# RotaryController2.net
KiCad netlist of a schematic drawn in Altium Designer
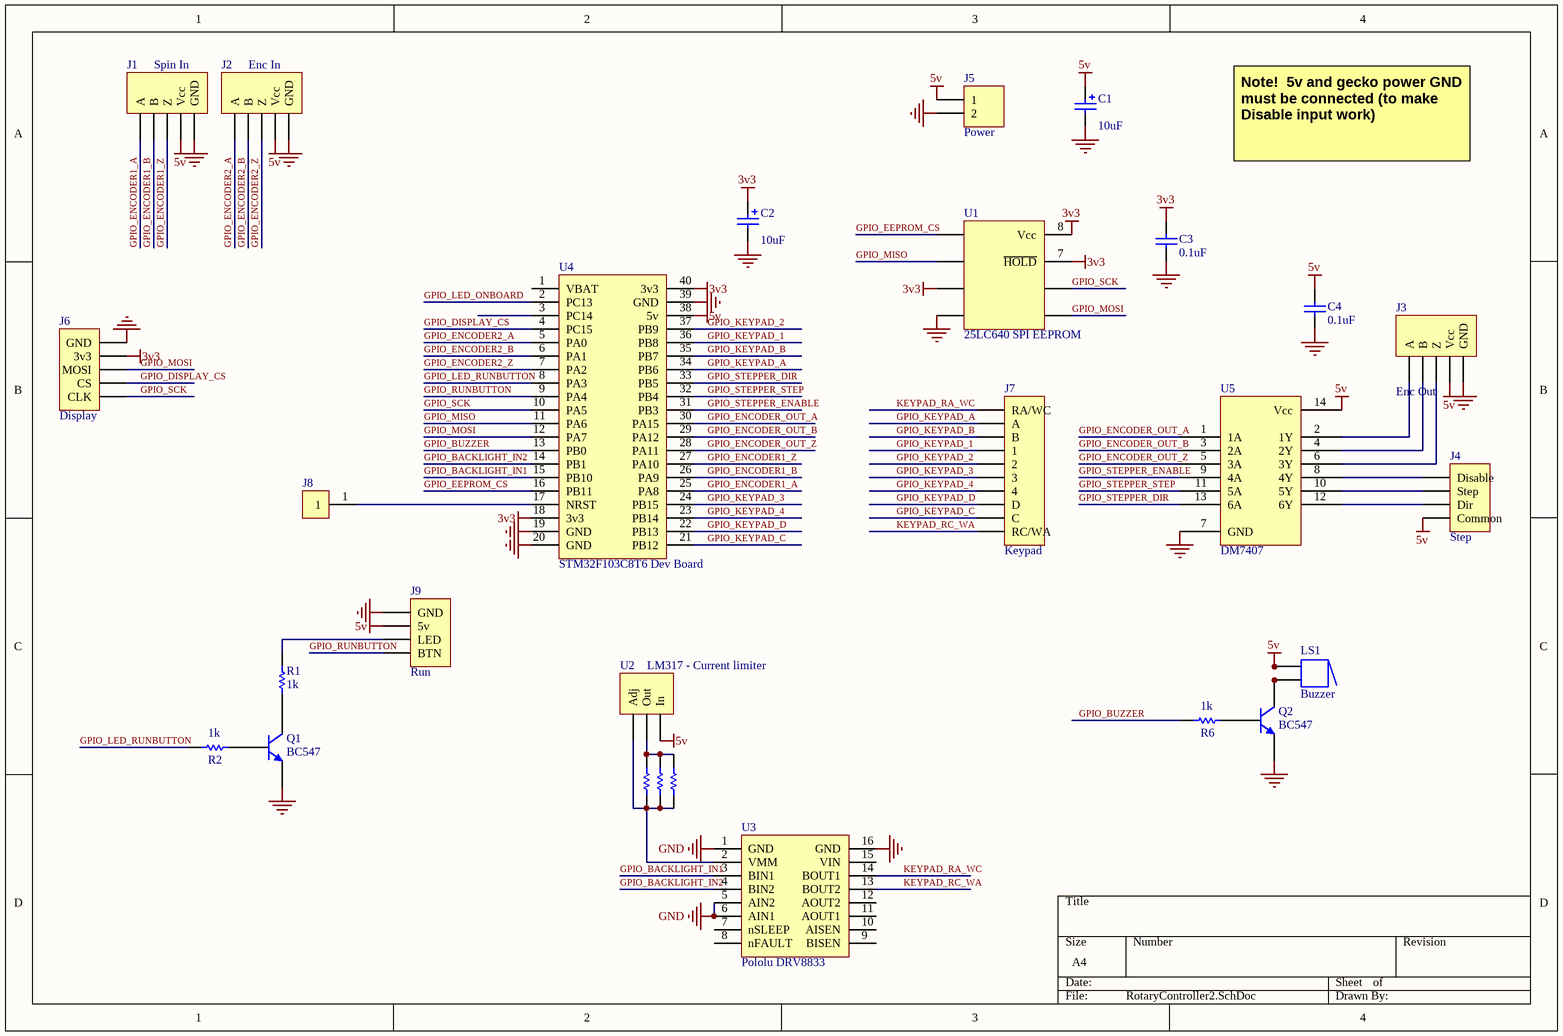
[diagram p0: RotaryController2.SchDoc]

(export (version "E")
  (design (tool "Eeschema 10.0.6"))
  (components
    (comp (ref "C1")
      (value "10uF")
      (footprint "Cap Cyl 14x5 2.5")
      (description "Polarized Capacitor (Radial)")
      (fields (field (name "Comment") "Cap Pol") (field (name "PUBLISHER") "Altium Limited"))
      (libsource (lib "Custom") (part "Cap Pol"))
    )
    (comp (ref "C2")
      (value "10uF")
      (footprint "Cap Cyl 14x5 2.5")
      (description "Polarized Capacitor (Radial)")
      (fields (field (name "Comment") "Cap Pol") (field (name "PUBLISHER") "Altium Limited"))
      (libsource (lib "Custom") (part "Cap Pol"))
    )
    (comp (ref "C3")
      (value "0.1uF")
      (footprint "Cap Monolithic 2.5")
      (description "Capacitor")
      (fields (field (name "Comment") "Cap") (field (name "PUBLISHER") "Altium Limited"))
      (libsource (lib "Custom") (part "Cap"))
    )
    (comp (ref "C4")
      (value "0.1uF")
      (footprint "Cap Monolithic 2.5")
      (description "Capacitor")
      (fields (field (name "Comment") "Cap") (field (name "PUBLISHER") "Altium Limited"))
      (libsource (lib "Custom") (part "Cap"))
    )
    (comp (ref "J1")
      (value "Spin In")
      (footprint "0.1 SIP 5 PIN")
      (description "Header, 5-Pin")
      (fields (field (name "PUBLISHER") "Altium Limited"))
      (libsource (lib "Miscellaneous Connectors") (part "Header 5"))
    )
    (comp (ref "J2")
      (value "Enc In")
      (footprint "0.1 SIP 5 PIN")
      (description "Header, 5-Pin")
      (fields (field (name "PUBLISHER") "Altium Limited"))
      (libsource (lib "Miscellaneous Connectors") (part "Header 5"))
    )
    (comp (ref "J3")
      (value "Enc Out")
      (footprint "0.1 SIP 5 PIN")
      (description "Header, 5-Pin")
      (fields (field (name "PUBLISHER") "Altium Limited"))
      (libsource (lib "Miscellaneous Connectors") (part "Header 5"))
    )
    (comp (ref "J4")
      (value "Step")
      (footprint "0.1 SIP 4 PIN")
      (description "Header, 4-Pin")
      (fields (field (name "PUBLISHER") "Altium Limited"))
      (libsource (lib "Miscellaneous Connectors") (part "Header 4"))
    )
    (comp (ref "J5")
      (value "Power")
      (footprint "0.156 SIP 2 PIN")
      (description "Header, 2-Pin")
      (fields (field (name "PUBLISHER") "Altium Limited"))
      (libsource (lib "Miscellaneous Connectors") (part "Header 2"))
    )
    (comp (ref "J6")
      (value "Display")
      (footprint "0.1 SIP 5 PIN")
      (description "Header, 5-Pin")
      (fields (field (name "PUBLISHER") "Altium Limited"))
      (libsource (lib "") (part "Header 5_1"))
    )
    (comp (ref "J7")
      (value "Keypad")
      (footprint "0.1 SIP 10 PIN")
      (description "Header, 10-Pin")
      (fields (field (name "PUBLISHER") "Altium Limited"))
      (libsource (lib "Miscellaneous Connectors") (part "Header 10"))
    )
    (comp (ref "J8") (value "HDR 1") (footprint "HDR1") (libsource (lib "Custom") (part "Header 1")))
    (comp (ref "J9")
      (value "Run")
      (footprint "0.1 SIP 4 PIN")
      (description "Header, 4-Pin")
      (fields (field (name "PUBLISHER") "Altium Limited"))
      (libsource (lib "Miscellaneous Connectors") (part "Header 4"))
    )
    (comp (ref "LS1")
      (value "Buzzer")
      (footprint "Buzzer Mini PC Mount Piezo 14x7.5")
      (description "Magnetic Transducer Buzzer")
      (fields (field (name "PUBLISHER") "Altium Limited"))
      (libsource (lib "Miscellaneous Devices") (part "Buzzer"))
    )
    (comp (ref "Q1")
      (value "BC547")
      (footprint "TO-92 0.05\"")
      (description "General Purpose Amplifier NPN Silicon")
      (fields (field (name "PUBLISHER") "Altium Limited"))
      (libsource (lib "Custom") (part "MMBT100A"))
    )
    (comp (ref "Q2")
      (value "BC547")
      (footprint "TO-92 0.05\"")
      (description "General Purpose Amplifier NPN Silicon")
      (fields (field (name "PUBLISHER") "Altium Limited"))
      (libsource (lib "Custom") (part "MMBT100A"))
    )
    (comp (ref "R1")
      (value "1k")
      (footprint "Resistor Axial 1/4W 0.4")
      (fields (field (name "Comment") "Res1"))
      (libsource (lib "Custom") (part "Resistor"))
    )
    (comp (ref "R2")
      (value "1k")
      (footprint "Resistor Axial 1/4W 0.4")
      (fields (field (name "Comment") "Res1"))
      (libsource (lib "Custom") (part "Resistor"))
    )
    (comp (ref "R3")
      (value "Res1")
      (footprint "Resistor Axial 1/4W 0.4")
      (libsource (lib "Custom") (part "Resistor"))
    )
    (comp (ref "R4")
      (value "Res1")
      (footprint "Resistor Axial 1/4W 0.4")
      (libsource (lib "Custom") (part "Resistor"))
    )
    (comp (ref "R5")
      (value "Res1")
      (footprint "Resistor Axial 1/4W 0.4")
      (libsource (lib "Custom") (part "Resistor"))
    )
    (comp (ref "R6")
      (value "1k")
      (footprint "Resistor Axial 1/4W 0.4")
      (fields (field (name "Comment") "Res1"))
      (libsource (lib "Custom") (part "Resistor"))
    )
    (comp (ref "U1")
      (value "25LC640 SPI EEPROM")
      (footprint "DIP8")
      (libsource (lib "Custom") (part "25LC640"))
    )
    (comp (ref "U2")
      (value "LM317 - Current limiter")
      (footprint "TO-220")
      (description "Header, 3-Pin")
      (fields (field (name "PUBLISHER") "Altium Limited"))
      (libsource (lib "Miscellaneous Connectors") (part "Header 3"))
    )
    (comp (ref "U3")
      (value "Pololu DRV8833")
      (footprint "Pololu DRV8833")
      (description "Pololu DRV8833 Dual Motor Driver Carrier")
      (libsource (lib "Custom") (part "Pololu DRV8833"))
    )
    (comp (ref "U4")
      (value "STM32F103C8T6 Dev Board")
      (footprint "STM32F103C8T6 Dev Board")
      (libsource (lib "Custom") (part "STM32F103C8T6 Dev Board"))
    )
    (comp (ref "U5")
      (value "DM7407")
      (footprint "DIP14")
      (description "Hex Buffer with Open Collector Outputs")
      (libsource (lib "Custom") (part "74xx07"))
    )
  )
  (nets
    (net (code "1") (name "/GPIO_BACKLIGHT_IN1") (class "Default")
      (node (ref "U3") (pin "3") (pinfunction "BIN1_3") (pintype "passive"))
      (node (ref "U4") (pin "15") (pinfunction "PB10_15") (pintype "passive"))
    )
    (net (code "2") (name "/GPIO_BACKLIGHT_IN2") (class "Default")
      (node (ref "U3") (pin "4") (pinfunction "BIN2_4") (pintype "passive"))
      (node (ref "U4") (pin "14") (pinfunction "PB1_14") (pintype "passive"))
    )
    (net (code "3") (name "/GPIO_BUZZER") (class "Default")
      (node (ref "R6") (pin "1") (pinfunction "1_1") (pintype "passive"))
      (node (ref "U4") (pin "13") (pinfunction "PB0_13") (pintype "passive"))
    )
    (net (code "4") (name "/GPIO_DISPLAY_CS") (class "Default")
      (node (ref "J6") (pin "2") (pinfunction "CS_2") (pintype "passive"))
      (node (ref "U4") (pin "4") (pinfunction "PC15_4") (pintype "passive"))
    )
    (net (code "5") (name "/GPIO_EEPROM_CS") (class "Default")
      (node (ref "U1") (pin "1") (pinfunction "~{CS}_1") (pintype "passive"))
      (node (ref "U4") (pin "16") (pinfunction "PB11_16") (pintype "passive"))
    )
    (net (code "6") (name "/GPIO_ENCODER1_A") (class "Default")
      (node (ref "J1") (pin "1") (pinfunction "A_1") (pintype "passive"))
      (node (ref "U4") (pin "25") (pinfunction "PA8_25") (pintype "passive"))
    )
    (net (code "7") (name "/GPIO_ENCODER1_B") (class "Default")
      (node (ref "J1") (pin "2") (pinfunction "B_2") (pintype "passive"))
      (node (ref "U4") (pin "26") (pinfunction "PA9_26") (pintype "passive"))
    )
    (net (code "8") (name "/GPIO_ENCODER1_Z") (class "Default")
      (node (ref "J1") (pin "3") (pinfunction "Z_3") (pintype "passive"))
      (node (ref "U4") (pin "27") (pinfunction "PA10_27") (pintype "passive"))
    )
    (net (code "9") (name "/GPIO_ENCODER2_A") (class "Default")
      (node (ref "J2") (pin "1") (pinfunction "A_1") (pintype "passive"))
      (node (ref "U4") (pin "5") (pinfunction "PA0_5") (pintype "passive"))
    )
    (net (code "10") (name "/GPIO_ENCODER2_B") (class "Default")
      (node (ref "J2") (pin "2") (pinfunction "B_2") (pintype "passive"))
      (node (ref "U4") (pin "6") (pinfunction "PA1_6") (pintype "passive"))
    )
    (net (code "11") (name "/GPIO_ENCODER2_Z") (class "Default")
      (node (ref "J2") (pin "3") (pinfunction "Z_3") (pintype "passive"))
      (node (ref "U4") (pin "7") (pinfunction "PA2_7") (pintype "passive"))
    )
    (net (code "12") (name "/GPIO_ENCODER_OUT_A") (class "Default")
      (node (ref "U4") (pin "30") (pinfunction "PA15_30") (pintype "passive"))
      (node (ref "U5") (pin "1") (pinfunction "1A_1") (pintype "passive"))
    )
    (net (code "13") (name "/GPIO_ENCODER_OUT_B") (class "Default")
      (node (ref "U4") (pin "29") (pinfunction "PA12_29") (pintype "passive"))
      (node (ref "U5") (pin "3") (pinfunction "2A_3") (pintype "passive"))
    )
    (net (code "14") (name "/GPIO_ENCODER_OUT_Z") (class "Default")
      (node (ref "U4") (pin "28") (pinfunction "PA11_28") (pintype "passive"))
      (node (ref "U5") (pin "5") (pinfunction "3A_5") (pintype "passive"))
    )
    (net (code "15") (name "/GPIO_KEYPAD_1") (class "Default")
      (node (ref "J7") (pin "4") (pinfunction "1_4") (pintype "passive"))
      (node (ref "U4") (pin "36") (pinfunction "PB8_36") (pintype "passive"))
    )
    (net (code "16") (name "/GPIO_KEYPAD_2") (class "Default")
      (node (ref "J7") (pin "5") (pinfunction "2_5") (pintype "passive"))
      (node (ref "U4") (pin "37") (pinfunction "PB9_37") (pintype "passive"))
    )
    (net (code "17") (name "/GPIO_KEYPAD_3") (class "Default")
      (node (ref "J7") (pin "6") (pinfunction "3_6") (pintype "passive"))
      (node (ref "U4") (pin "24") (pinfunction "PB15_24") (pintype "passive"))
    )
    (net (code "18") (name "/GPIO_KEYPAD_4") (class "Default")
      (node (ref "J7") (pin "7") (pinfunction "4_7") (pintype "passive"))
      (node (ref "U4") (pin "23") (pinfunction "PB14_23") (pintype "passive"))
    )
    (net (code "19") (name "/GPIO_KEYPAD_A") (class "Default")
      (node (ref "J7") (pin "2") (pinfunction "A_2") (pintype "passive"))
      (node (ref "U4") (pin "34") (pinfunction "PB6_34") (pintype "passive"))
    )
    (net (code "20") (name "/GPIO_KEYPAD_B") (class "Default")
      (node (ref "J7") (pin "3") (pinfunction "B_3") (pintype "passive"))
      (node (ref "U4") (pin "35") (pinfunction "PB7_35") (pintype "passive"))
    )
    (net (code "21") (name "/GPIO_KEYPAD_C") (class "Default")
      (node (ref "J7") (pin "9") (pinfunction "C_9") (pintype "passive"))
      (node (ref "U4") (pin "21") (pinfunction "PB12_21") (pintype "passive"))
    )
    (net (code "22") (name "/GPIO_KEYPAD_D") (class "Default")
      (node (ref "J7") (pin "8") (pinfunction "D_8") (pintype "passive"))
      (node (ref "U4") (pin "22") (pinfunction "PB13_22") (pintype "passive"))
    )
    (net (code "23") (name "/GPIO_LED_ONBOARD") (class "Default")
      (node (ref "U4") (pin "2") (pinfunction "PC13_2") (pintype "passive"))
    )
    (net (code "24") (name "/GPIO_LED_RUNBUTTON") (class "Default")
      (node (ref "R2") (pin "1") (pinfunction "1_1") (pintype "passive"))
      (node (ref "U4") (pin "8") (pinfunction "PA3_8") (pintype "passive"))
    )
    (net (code "25") (name "/GPIO_MISO") (class "Default")
      (node (ref "U1") (pin "2") (pinfunction "SO_2") (pintype "passive"))
      (node (ref "U4") (pin "11") (pinfunction "PA6_11") (pintype "passive"))
    )
    (net (code "26") (name "/GPIO_MOSI") (class "Default")
      (node (ref "J6") (pin "3") (pinfunction "MOSI_3") (pintype "passive"))
      (node (ref "U1") (pin "5") (pinfunction "SI_5") (pintype "passive"))
      (node (ref "U4") (pin "12") (pinfunction "PA7_12") (pintype "passive"))
    )
    (net (code "27") (name "/GPIO_RUNBUTTON") (class "Default")
      (node (ref "J9") (pin "4") (pinfunction "Common_4") (pintype "passive"))
      (node (ref "U4") (pin "9") (pinfunction "PA4_9") (pintype "passive"))
    )
    (net (code "28") (name "/GPIO_SCK") (class "Default")
      (node (ref "J6") (pin "1") (pinfunction "CLK_1") (pintype "passive"))
      (node (ref "U1") (pin "6") (pinfunction "SCK_6") (pintype "passive"))
      (node (ref "U4") (pin "10") (pinfunction "PA5_10") (pintype "passive"))
    )
    (net (code "29") (name "/GPIO_STEPPER_DIR") (class "Default")
      (node (ref "U4") (pin "33") (pinfunction "PB5_33") (pintype "passive"))
      (node (ref "U5") (pin "13") (pinfunction "6A_13") (pintype "passive"))
    )
    (net (code "30") (name "/GPIO_STEPPER_ENABLE") (class "Default")
      (node (ref "U4") (pin "31") (pinfunction "PB3_31") (pintype "passive"))
      (node (ref "U5") (pin "9") (pinfunction "4A_9") (pintype "passive"))
    )
    (net (code "31") (name "/GPIO_STEPPER_STEP") (class "Default")
      (node (ref "U4") (pin "32") (pinfunction "PB4_32") (pintype "passive"))
      (node (ref "U5") (pin "11") (pinfunction "5A_11") (pintype "passive"))
    )
    (net (code "32") (name "/KEYPAD_RA_WC") (class "Default")
      (node (ref "J7") (pin "1") (pinfunction "RA/WC_1") (pintype "passive"))
      (node (ref "U3") (pin "14") (pinfunction "BOUT1_14") (pintype "passive"))
    )
    (net (code "33") (name "/KEYPAD_RC_WA") (class "Default")
      (node (ref "J7") (pin "10") (pinfunction "RC/WA_10") (pintype "passive"))
      (node (ref "U3") (pin "13") (pinfunction "BOUT2_13") (pintype "passive"))
    )
    (net (code "34") (name "3v3") (class "Default")
      (node (ref "C2") (pin "1") (pinfunction "1_1") (pintype "passive"))
      (node (ref "C3") (pin "2") (pinfunction "2_2") (pintype "passive"))
      (node (ref "J6") (pin "4") (pinfunction "3v3_4") (pintype "passive"))
      (node (ref "U1") (pin "3") (pinfunction "~{WP}_3") (pintype "passive"))
      (node (ref "U1") (pin "7") (pinfunction "~{HOLD}_7") (pintype "power_in"))
      (node (ref "U1") (pin "8") (pinfunction "Vcc_8") (pintype "power_in"))
      (node (ref "U4") (pin "18") (pinfunction "3v3_18") (pintype "passive"))
      (node (ref "U4") (pin "40") (pinfunction "3v3_40") (pintype "passive"))
    )
    (net (code "35") (name "5v") (class "Default")
      (node (ref "C1") (pin "1") (pinfunction "1_1") (pintype "passive"))
      (node (ref "C4") (pin "2") (pinfunction "2_2") (pintype "passive"))
      (node (ref "J1") (pin "4") (pinfunction "Vcc_4") (pintype "passive"))
      (node (ref "J2") (pin "4") (pinfunction "Vcc_4") (pintype "passive"))
      (node (ref "J3") (pin "4") (pinfunction "Vcc_4") (pintype "passive"))
      (node (ref "J4") (pin "4") (pinfunction "Common_4") (pintype "passive"))
      (node (ref "J5") (pin "1") (pinfunction "1_1") (pintype "passive"))
      (node (ref "J9") (pin "2") (pinfunction "Step_2") (pintype "passive"))
      (node (ref "LS1") (pin "1") (pinfunction "1_1") (pintype "passive"))
      (node (ref "LS1") (pin "1A") (pinfunction "1A_1A") (pintype "passive"))
      (node (ref "U2") (pin "3") (pinfunction "In_3") (pintype "passive"))
      (node (ref "U4") (pin "38") (pinfunction "5v_38") (pintype "passive"))
      (node (ref "U5") (pin "14") (pinfunction "Vcc_14") (pintype "passive"))
    )
    (net (code "36") (name "GND") (class "Default")
      (node (ref "C1") (pin "2") (pinfunction "2_2") (pintype "passive"))
      (node (ref "C2") (pin "2") (pinfunction "2_2") (pintype "passive"))
      (node (ref "C3") (pin "1") (pinfunction "1_1") (pintype "passive"))
      (node (ref "C4") (pin "1") (pinfunction "1_1") (pintype "passive"))
      (node (ref "J1") (pin "5") (pinfunction "GND_5") (pintype "passive"))
      (node (ref "J2") (pin "5") (pinfunction "GND_5") (pintype "passive"))
      (node (ref "J3") (pin "5") (pinfunction "GND_5") (pintype "passive"))
      (node (ref "J5") (pin "2") (pinfunction "2_2") (pintype "passive"))
      (node (ref "J6") (pin "5") (pinfunction "GND_5") (pintype "passive"))
      (node (ref "J9") (pin "1") (pinfunction "Disable_1") (pintype "passive"))
      (node (ref "Q1") (pin "E") (pinfunction "E_E") (pintype "passive"))
      (node (ref "Q2") (pin "E") (pinfunction "E_E") (pintype "passive"))
      (node (ref "U1") (pin "4") (pinfunction "Vss_4") (pintype "passive"))
      (node (ref "U3") (pin "1") (pinfunction "GND_1") (pintype "passive"))
      (node (ref "U3") (pin "16") (pinfunction "GND_16") (pintype "passive"))
      (node (ref "U3") (pin "5") (pinfunction "AIN2_5") (pintype "passive"))
      (node (ref "U3") (pin "6") (pinfunction "AIN1_6") (pintype "passive"))
      (node (ref "U4") (pin "19") (pinfunction "GND_19") (pintype "passive"))
      (node (ref "U4") (pin "20") (pinfunction "GND_20") (pintype "passive"))
      (node (ref "U4") (pin "39") (pinfunction "GND_39") (pintype "passive"))
      (node (ref "U5") (pin "7") (pinfunction "GND_7") (pintype "passive"))
    )
    (net (code "37") (name "Net-(J3-A)") (class "Default")
      (node (ref "J3") (pin "1") (pinfunction "A_1") (pintype "passive"))
      (node (ref "U5") (pin "2") (pinfunction "1Y_2") (pintype "passive"))
    )
    (net (code "38") (name "Net-(J3-B)") (class "Default")
      (node (ref "J3") (pin "2") (pinfunction "B_2") (pintype "passive"))
      (node (ref "U5") (pin "4") (pinfunction "2Y_4") (pintype "passive"))
    )
    (net (code "39") (name "Net-(J3-Z)") (class "Default")
      (node (ref "J3") (pin "3") (pinfunction "Z_3") (pintype "passive"))
      (node (ref "U5") (pin "6") (pinfunction "3Y_6") (pintype "passive"))
    )
    (net (code "40") (name "Net-(J4-Dir)") (class "Default")
      (node (ref "J4") (pin "3") (pinfunction "Dir_3") (pintype "passive"))
      (node (ref "U5") (pin "12") (pinfunction "6Y_12") (pintype "passive"))
    )
    (net (code "41") (name "Net-(J4-Disable)") (class "Default")
      (node (ref "J4") (pin "1") (pinfunction "Disable_1") (pintype "passive"))
      (node (ref "U5") (pin "8") (pinfunction "4Y_8") (pintype "passive"))
    )
    (net (code "42") (name "Net-(J4-Step)") (class "Default")
      (node (ref "J4") (pin "2") (pinfunction "Step_2") (pintype "passive"))
      (node (ref "U5") (pin "10") (pinfunction "5Y_10") (pintype "passive"))
    )
    (net (code "43") (name "Net-(J9-Dir)") (class "Default")
      (node (ref "J9") (pin "3") (pinfunction "Dir_3") (pintype "passive"))
      (node (ref "R1") (pin "1") (pinfunction "1_1") (pintype "passive"))
    )
    (net (code "44") (name "Net-(LS1-Pad2)") (class "Default")
      (node (ref "LS1") (pin "2") (pinfunction "2_2") (pintype "passive"))
      (node (ref "LS1") (pin "2A") (pinfunction "2A_2A") (pintype "passive"))
      (node (ref "Q2") (pin "C") (pinfunction "C_C") (pintype "passive"))
    )
    (net (code "45") (name "Net-(Q1-PadB)") (class "Default")
      (node (ref "Q1") (pin "B") (pinfunction "B_B") (pintype "passive"))
      (node (ref "R2") (pin "2") (pinfunction "2_2") (pintype "passive"))
    )
    (net (code "46") (name "Net-(Q1-PadC)") (class "Default")
      (node (ref "Q1") (pin "C") (pinfunction "C_C") (pintype "passive"))
      (node (ref "R1") (pin "2") (pinfunction "2_2") (pintype "passive"))
    )
    (net (code "47") (name "Net-(Q2-PadB)") (class "Default")
      (node (ref "Q2") (pin "B") (pinfunction "B_B") (pintype "passive"))
      (node (ref "R6") (pin "2") (pinfunction "2_2") (pintype "passive"))
    )
    (net (code "48") (name "Net-(U2-Adj)") (class "Default")
      (node (ref "R3") (pin "2") (pinfunction "2_2") (pintype "passive"))
      (node (ref "R4") (pin "2") (pinfunction "2_2") (pintype "passive"))
      (node (ref "R5") (pin "2") (pinfunction "2_2") (pintype "passive"))
      (node (ref "U2") (pin "1") (pinfunction "Adj_1") (pintype "passive"))
      (node (ref "U3") (pin "2") (pinfunction "VMM_2") (pintype "passive"))
    )
    (net (code "49") (name "Net-(U2-Out)") (class "Default")
      (node (ref "R3") (pin "1") (pinfunction "1_1") (pintype "passive"))
      (node (ref "R4") (pin "1") (pinfunction "1_1") (pintype "passive"))
      (node (ref "R5") (pin "1") (pinfunction "1_1") (pintype "passive"))
      (node (ref "U2") (pin "2") (pinfunction "Out_2") (pintype "passive"))
    )
    (net (code "50") (name "Net-(U4-NRST)") (class "Default")
      (node (ref "J8") (pin "1") (pinfunction "1_1") (pintype "passive"))
      (node (ref "U4") (pin "17") (pinfunction "NRST_17") (pintype "passive"))
    )
    (net (code "51") (name "unconnected-(U3-AISEN-Pad10)") (class "Default")
      (node (ref "U3") (pin "10") (pinfunction "AISEN_10") (pintype "passive"))
    )
    (net (code "52") (name "unconnected-(U3-AOUT1-Pad11)") (class "Default")
      (node (ref "U3") (pin "11") (pinfunction "AOUT1_11") (pintype "passive"))
    )
    (net (code "53") (name "unconnected-(U3-AOUT2-Pad12)") (class "Default")
      (node (ref "U3") (pin "12") (pinfunction "AOUT2_12") (pintype "passive"))
    )
    (net (code "54") (name "unconnected-(U3-BISEN-Pad9)") (class "Default")
      (node (ref "U3") (pin "9") (pinfunction "BISEN_9") (pintype "passive"))
    )
    (net (code "55") (name "unconnected-(U3-VIN-Pad15)") (class "Default")
      (node (ref "U3") (pin "15") (pinfunction "VIN_15") (pintype "passive"))
    )
    (net (code "56") (name "unconnected-(U3-nFAULT-Pad8)") (class "Default")
      (node (ref "U3") (pin "8") (pinfunction "nFAULT_8") (pintype "passive"))
    )
    (net (code "57") (name "unconnected-(U3-nSLEEP-Pad7)") (class "Default")
      (node (ref "U3") (pin "7") (pinfunction "nSLEEP_7") (pintype "passive"))
    )
    (net (code "58") (name "unconnected-(U4-PC14-Pad3)") (class "Default")
      (node (ref "U4") (pin "3") (pinfunction "PC14_3") (pintype "passive"))
    )
    (net (code "59") (name "unconnected-(U4-VBAT-Pad1)") (class "Default")
      (node (ref "U4") (pin "1") (pinfunction "VBAT_1") (pintype "passive"))
    )
  )
)
